# Mirror_TurnSignal.net
KiCad netlist of a schematic drawn in Altium Designer
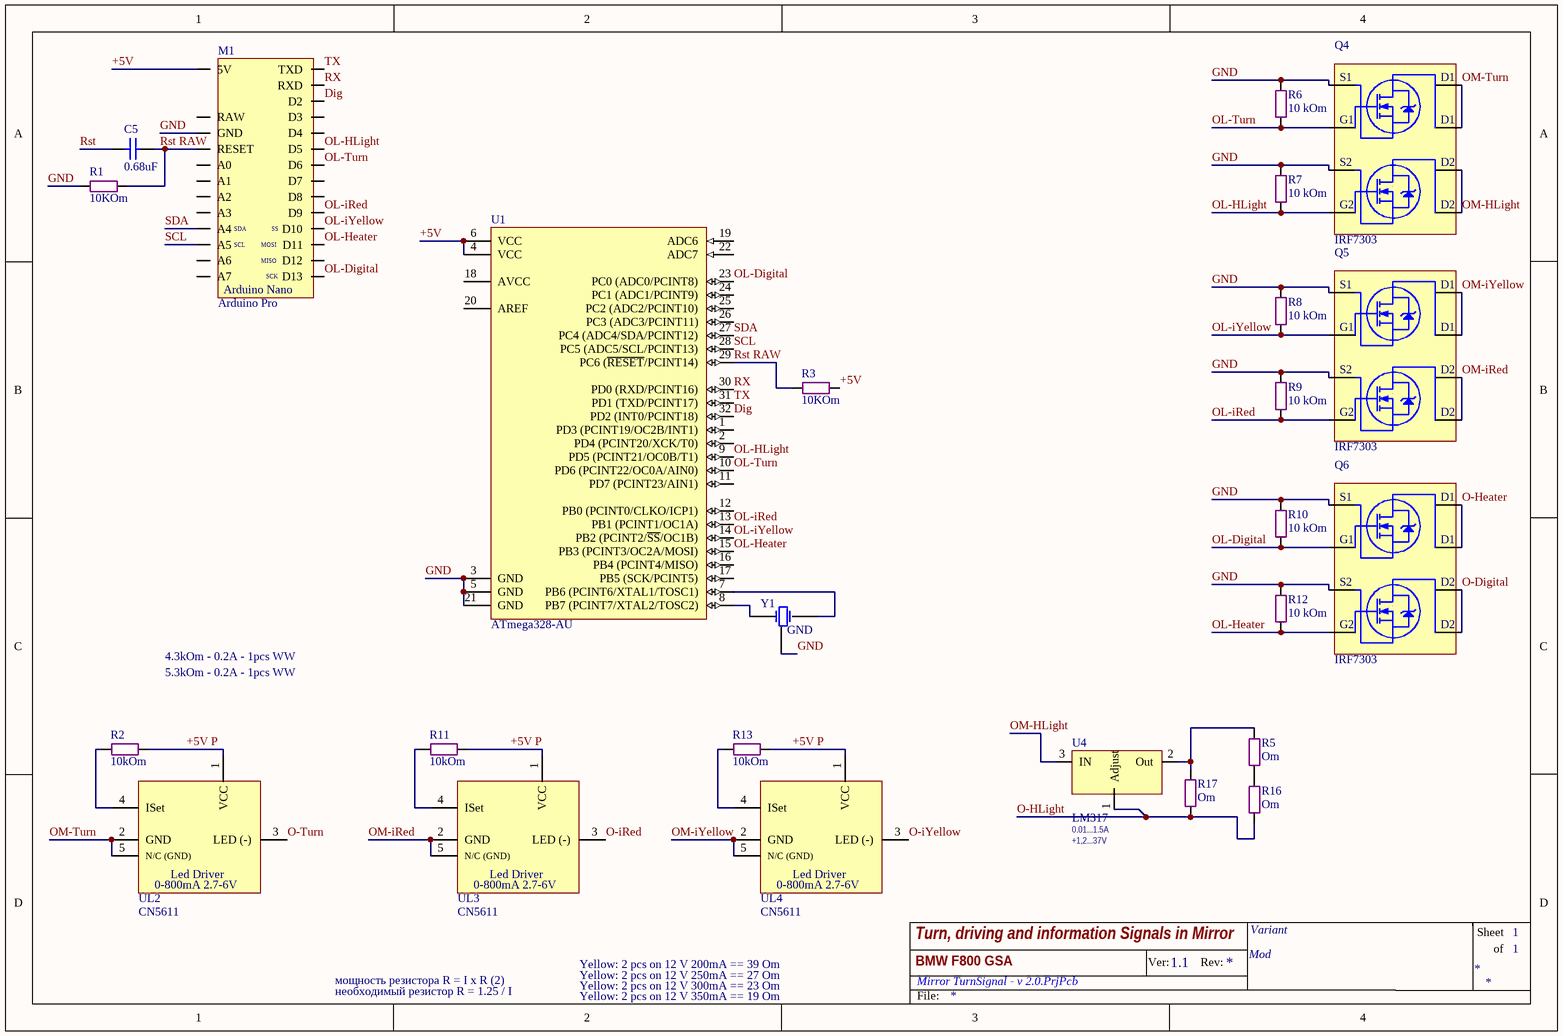
[diagram p0: Mirror TurnSignal.SchDoc]

(export (version "E")
  (design (tool "Eeschema 10.0.6"))
  (components
    (comp (ref "C5")
      (value "0.68uF")
      (footprint "Capacitor:SMD 0805 (2012)")
      (description "Capacitor")
      (libsource (lib "Capacitor") (part "Cap SMD 0402-1812"))
    )
    (comp (ref "M1")
      (value "Arduino Pro")
      (footprint "Modules:Arduino Pro Mini Low (no A0-3,6-7,D3)")
      (libsource (lib "Modules") (part "Arduino Pro Micro"))
    )
    (comp (ref "Q4")
      (value "IRF7303")
      (footprint "GeneralCases:SO8")
      (description "Dual N-Ch  30V - 0.05Ω - 4.9A")
      (fields (field (name "MANUFACTURER") "Farchild"))
      (libsource (lib "Transistor") (part "IRF7303"))
    )
    (comp (ref "Q5")
      (value "IRF7303")
      (footprint "GeneralCases:SO8")
      (description "Dual N-Ch  30V - 0.05Ω - 4.9A")
      (fields (field (name "MANUFACTURER") "Farchild"))
      (libsource (lib "Transistor") (part "IRF7303"))
    )
    (comp (ref "Q6")
      (value "IRF7303")
      (footprint "GeneralCases:SO8")
      (description "Dual N-Ch  30V - 0.05Ω - 4.9A")
      (fields (field (name "MANUFACTURER") "Farchild"))
      (libsource (lib "Transistor") (part "IRF7303"))
    )
    (comp (ref "R1")
      (value "10KOm")
      (footprint "PassiveComponents:SMD 0805 (2012)")
      (libsource (lib "PassiveComponents") (part "Res All Types"))
    )
    (comp (ref "R2")
      (value "10kOm")
      (footprint "PassiveComponents:SMD 0805 (2012)")
      (libsource (lib "PassiveComponents") (part "Res All Types"))
    )
    (comp (ref "R3")
      (value "10KOm")
      (footprint "PassiveComponents:SMD 0805 (2012)")
      (libsource (lib "PassiveComponents") (part "Res All Types"))
    )
    (comp (ref "R5")
      (value "Om")
      (footprint "PassiveComponents:Res 5W L22mm, p22.86")
      (description "5W Cement")
      (libsource (lib "PassiveComponents") (part "Res 5W"))
    )
    (comp (ref "R6")
      (value "10 kOm")
      (footprint "PassiveComponents:SMD 0805 (2012)")
      (libsource (lib "PassiveComponents") (part "Res All Types"))
    )
    (comp (ref "R7")
      (value "10 kOm")
      (footprint "PassiveComponents:SMD 0805 (2012)")
      (libsource (lib "PassiveComponents") (part "Res All Types"))
    )
    (comp (ref "R8")
      (value "10 kOm")
      (footprint "PassiveComponents:SMD 0805 (2012)")
      (libsource (lib "PassiveComponents") (part "Res All Types"))
    )
    (comp (ref "R9")
      (value "10 kOm")
      (footprint "PassiveComponents:SMD 0805 (2012)")
      (libsource (lib "PassiveComponents") (part "Res All Types"))
    )
    (comp (ref "R10")
      (value "10 kOm")
      (footprint "PassiveComponents:SMD 0805 (2012)")
      (libsource (lib "PassiveComponents") (part "Res All Types"))
    )
    (comp (ref "R11")
      (value "10kOm")
      (footprint "PassiveComponents:SMD 0805 (2012)")
      (libsource (lib "PassiveComponents") (part "Res All Types"))
    )
    (comp (ref "R12")
      (value "10 kOm")
      (footprint "PassiveComponents:SMD 0805 (2012)")
      (libsource (lib "PassiveComponents") (part "Res All Types"))
    )
    (comp (ref "R13")
      (value "10kOm")
      (footprint "PassiveComponents:SMD 0805 (2012)")
      (libsource (lib "PassiveComponents") (part "Res All Types"))
    )
    (comp (ref "R16")
      (value "Om")
      (footprint "PassiveComponents:Res 5W L22mm, p22.86")
      (description "5W Cement")
      (libsource (lib "PassiveComponents") (part "Res 5W"))
    )
    (comp (ref "R17")
      (value "Om")
      (footprint "PassiveComponents:Res 10W L48mm, p49mm")
      (description "10W Cement")
      (libsource (lib "PassiveComponents") (part "Res 10W"))
    )
    (comp (ref "U1")
      (value "ATmega328-AU")
      (footprint "32A_M")
      (fields (field (name "PUBLISHER") "Altium Limited"))
      (libsource (lib "Atmel Microcontroller 8-Bit megaAVR") (part "ATmega328-AU"))
    )
    (comp (ref "U4")
      (value "LM317")
      (footprint "GeneralCases:TO220 L")
      (description "Voltage Regulator")
      (fields (field (name "I OUTPUT (A) ADJUSTABLE") "0.01...1.5A") (field (name "V OUT") "+1,2...37V"))
      (libsource (lib "PowerAdjusment") (part "LM-317"))
    )
    (comp (ref "UL2")
      (value "CN5611")
      (footprint "GeneralCases:SOT-89-5")
      (description "Led Driver 0-800mA 2.7-6V")
      (fields (field (name "NAME") "CN5611"))
      (libsource (lib "Chips") (part "CN5611"))
    )
    (comp (ref "UL3")
      (value "CN5611")
      (footprint "GeneralCases:SOT-89-5")
      (description "Led Driver 0-800mA 2.7-6V")
      (fields (field (name "NAME") "CN5611"))
      (libsource (lib "Chips") (part "CN5611"))
    )
    (comp (ref "UL4")
      (value "CN5611")
      (footprint "GeneralCases:SOT-89-5")
      (description "Led Driver 0-800mA 2.7-6V")
      (fields (field (name "NAME") "CN5611"))
      (libsource (lib "Chips") (part "CN5611"))
    )
    (comp (ref "Y1")
      (value "16MHz")
      (footprint "PassiveComponents:XTAL - 3.2x1.2 SMD ws GND")
      (description "3 Pin with Capacitors")
      (libsource (lib "PassiveComponents") (part "XTAL ws CAP"))
    )
  )
  (nets
    (net (code "1") (name "/+5V") (class "Default")
      (node (ref "M1") (pin "5V") (pinfunction "5V_5V") (pintype "passive"))
      (node (ref "R3") (pin "2") (pinfunction "2_2") (pintype "passive"))
      (node (ref "U1") (pin "4") (pinfunction "VCC_4") (pintype "power_in"))
      (node (ref "U1") (pin "6") (pinfunction "VCC_6") (pintype "power_in"))
    )
    (net (code "2") (name "/+5V P") (class "Default")
      (node (ref "R11") (pin "1") (pinfunction "1_1") (pintype "passive"))
      (node (ref "R13") (pin "1") (pinfunction "1_1") (pintype "passive"))
      (node (ref "R2") (pin "1") (pinfunction "1_1") (pintype "passive"))
      (node (ref "UL2") (pin "1") (pinfunction "VCC_1") (pintype "power_in"))
      (node (ref "UL3") (pin "1") (pinfunction "VCC_1") (pintype "power_in"))
      (node (ref "UL4") (pin "1") (pinfunction "VCC_1") (pintype "power_in"))
    )
    (net (code "3") (name "/Dig") (class "Default")
      (node (ref "M1") (pin "D2") (pinfunction "D2_D2") (pintype "passive"))
      (node (ref "U1") (pin "32") (pinfunction "PD2_(INT0/PCINT18)_32") (pintype "bidirectional"))
    )
    (net (code "4") (name "/GND") (class "Default")
      (node (ref "M1") (pin "GND") (pinfunction "GND_GND") (pintype "passive"))
      (node (ref "Q4") (pin "1") (pinfunction "S_1") (pintype "passive"))
      (node (ref "Q4") (pin "3") (pinfunction "S_3") (pintype "passive"))
      (node (ref "Q5") (pin "1") (pinfunction "S_1") (pintype "passive"))
      (node (ref "Q5") (pin "3") (pinfunction "S_3") (pintype "passive"))
      (node (ref "Q6") (pin "1") (pinfunction "S_1") (pintype "passive"))
      (node (ref "Q6") (pin "3") (pinfunction "S_3") (pintype "passive"))
      (node (ref "R1") (pin "1") (pinfunction "1_1") (pintype "passive"))
      (node (ref "R10") (pin "2") (pinfunction "2_2") (pintype "passive"))
      (node (ref "R12") (pin "2") (pinfunction "2_2") (pintype "passive"))
      (node (ref "R6") (pin "2") (pinfunction "2_2") (pintype "passive"))
      (node (ref "R7") (pin "2") (pinfunction "2_2") (pintype "passive"))
      (node (ref "R8") (pin "2") (pinfunction "2_2") (pintype "passive"))
      (node (ref "R9") (pin "2") (pinfunction "2_2") (pintype "passive"))
      (node (ref "U1") (pin "21") (pinfunction "GND_21") (pintype "power_in"))
      (node (ref "U1") (pin "3") (pinfunction "GND_3") (pintype "power_in"))
      (node (ref "U1") (pin "5") (pinfunction "GND_5") (pintype "power_in"))
      (node (ref "Y1") (pin "3") (pinfunction "GND_3") (pintype "passive"))
    )
    (net (code "5") (name "/O-Digital") (class "Default")
      (node (ref "Q6") (pin "5") (pinfunction "D_5") (pintype "passive"))
      (node (ref "Q6") (pin "6") (pinfunction "D_6") (pintype "passive"))
    )
    (net (code "6") (name "/O-HLight") (class "Default")
      (node (ref "R16") (pin "1") (pinfunction "1_1") (pintype "passive"))
      (node (ref "R17") (pin "1") (pinfunction "1_1") (pintype "passive"))
      (node (ref "U4") (pin "1") (pinfunction "Adjust_1") (pintype "passive"))
    )
    (net (code "7") (name "/O-Heater") (class "Default")
      (node (ref "Q6") (pin "7") (pinfunction "D_7") (pintype "passive"))
      (node (ref "Q6") (pin "8") (pinfunction "D_8") (pintype "passive"))
    )
    (net (code "8") (name "/O-Turn") (class "Default")
      (node (ref "UL2") (pin "3") (pinfunction "LED_(-)_3") (pintype "power_in"))
    )
    (net (code "9") (name "/O-iRed") (class "Default")
      (node (ref "UL3") (pin "3") (pinfunction "LED_(-)_3") (pintype "power_in"))
    )
    (net (code "10") (name "/O-iYellow") (class "Default")
      (node (ref "UL4") (pin "3") (pinfunction "LED_(-)_3") (pintype "power_in"))
    )
    (net (code "11") (name "/OL-Digital") (class "Default")
      (node (ref "M1") (pin "D13") (pinfunction "D13_D13") (pintype "passive"))
      (node (ref "Q6") (pin "2") (pinfunction "G_2") (pintype "passive"))
      (node (ref "R10") (pin "1") (pinfunction "1_1") (pintype "passive"))
      (node (ref "U1") (pin "23") (pinfunction "PC0_(ADC0/PCINT8)_23") (pintype "bidirectional"))
    )
    (net (code "12") (name "/OL-HLight") (class "Default")
      (node (ref "M1") (pin "D5") (pinfunction "D5_D5") (pintype "passive"))
      (node (ref "Q4") (pin "4") (pinfunction "G_4") (pintype "passive"))
      (node (ref "R7") (pin "1") (pinfunction "1_1") (pintype "passive"))
      (node (ref "U1") (pin "9") (pinfunction "PD5_(PCINT21/OC0B/T1)_9") (pintype "bidirectional"))
    )
    (net (code "13") (name "/OL-Heater") (class "Default")
      (node (ref "M1") (pin "D11") (pinfunction "D11_D11") (pintype "passive"))
      (node (ref "Q6") (pin "4") (pinfunction "G_4") (pintype "passive"))
      (node (ref "R12") (pin "1") (pinfunction "1_1") (pintype "passive"))
      (node (ref "U1") (pin "15") (pinfunction "PB3_(PCINT3/OC2A/MOSI)_15") (pintype "bidirectional"))
    )
    (net (code "14") (name "/OL-Turn") (class "Default")
      (node (ref "M1") (pin "D6") (pinfunction "D6_D6") (pintype "passive"))
      (node (ref "Q4") (pin "2") (pinfunction "G_2") (pintype "passive"))
      (node (ref "R6") (pin "1") (pinfunction "1_1") (pintype "passive"))
      (node (ref "U1") (pin "10") (pinfunction "PD6_(PCINT22/OC0A/AIN0)_10") (pintype "bidirectional"))
    )
    (net (code "15") (name "/OL-iRed") (class "Default")
      (node (ref "M1") (pin "D9") (pinfunction "D9_D9") (pintype "passive"))
      (node (ref "Q5") (pin "4") (pinfunction "G_4") (pintype "passive"))
      (node (ref "R9") (pin "1") (pinfunction "1_1") (pintype "passive"))
      (node (ref "U1") (pin "13") (pinfunction "PB1_(PCINT1/OC1A)_13") (pintype "bidirectional"))
    )
    (net (code "16") (name "/OL-iYellow") (class "Default")
      (node (ref "M1") (pin "D10") (pinfunction "D10_D10") (pintype "passive"))
      (node (ref "Q5") (pin "2") (pinfunction "G_2") (pintype "passive"))
      (node (ref "R8") (pin "1") (pinfunction "1_1") (pintype "passive"))
      (node (ref "U1") (pin "14") (pinfunction "PB2_(PCINT2/~{SS}/OC1B)_14") (pintype "bidirectional"))
    )
    (net (code "17") (name "/OM-HLight") (class "Default")
      (node (ref "Q4") (pin "5") (pinfunction "D_5") (pintype "passive"))
      (node (ref "Q4") (pin "6") (pinfunction "D_6") (pintype "passive"))
      (node (ref "U4") (pin "3") (pinfunction "IN_3") (pintype "power_in"))
    )
    (net (code "18") (name "/OM-Turn") (class "Default")
      (node (ref "Q4") (pin "7") (pinfunction "D_7") (pintype "passive"))
      (node (ref "Q4") (pin "8") (pinfunction "D_8") (pintype "passive"))
      (node (ref "UL2") (pin "2") (pinfunction "GND_2") (pintype "power_in"))
      (node (ref "UL2") (pin "5") (pinfunction "N/C_(GND)_5") (pintype "power_in"))
    )
    (net (code "19") (name "/OM-iRed") (class "Default")
      (node (ref "Q5") (pin "5") (pinfunction "D_5") (pintype "passive"))
      (node (ref "Q5") (pin "6") (pinfunction "D_6") (pintype "passive"))
      (node (ref "UL3") (pin "2") (pinfunction "GND_2") (pintype "power_in"))
      (node (ref "UL3") (pin "5") (pinfunction "N/C_(GND)_5") (pintype "power_in"))
    )
    (net (code "20") (name "/OM-iYellow") (class "Default")
      (node (ref "Q5") (pin "7") (pinfunction "D_7") (pintype "passive"))
      (node (ref "Q5") (pin "8") (pinfunction "D_8") (pintype "passive"))
      (node (ref "UL4") (pin "2") (pinfunction "GND_2") (pintype "power_in"))
      (node (ref "UL4") (pin "5") (pinfunction "N/C_(GND)_5") (pintype "power_in"))
    )
    (net (code "21") (name "/RX") (class "Default")
      (node (ref "M1") (pin "RXD") (pinfunction "RXD_RXD") (pintype "passive"))
      (node (ref "U1") (pin "30") (pinfunction "PD0_(RXD/PCINT16)_30") (pintype "bidirectional"))
    )
    (net (code "22") (name "/Rst") (class "Default")
      (node (ref "C5") (pin "1") (pinfunction "1_1") (pintype "passive"))
    )
    (net (code "23") (name "/Rst RAW") (class "Default")
      (node (ref "C5") (pin "2") (pinfunction "2_2") (pintype "passive"))
      (node (ref "M1") (pin "RESET") (pinfunction "RESET_RESET") (pintype "passive"))
      (node (ref "R1") (pin "2") (pinfunction "2_2") (pintype "passive"))
      (node (ref "R3") (pin "1") (pinfunction "1_1") (pintype "passive"))
      (node (ref "U1") (pin "29") (pinfunction "PC6_(~{RESET}/PCINT14)_29") (pintype "bidirectional"))
    )
    (net (code "24") (name "/SCL") (class "Default")
      (node (ref "M1") (pin "A5") (pinfunction "A5_A5") (pintype "passive"))
      (node (ref "U1") (pin "28") (pinfunction "PC5_(ADC5/SCL/PCINT13)_28") (pintype "bidirectional"))
    )
    (net (code "25") (name "/SDA") (class "Default")
      (node (ref "M1") (pin "A4") (pinfunction "A4_A4") (pintype "passive"))
      (node (ref "U1") (pin "27") (pinfunction "PC4_(ADC4/SDA/PCINT12)_27") (pintype "bidirectional"))
    )
    (net (code "26") (name "/TX") (class "Default")
      (node (ref "M1") (pin "TXD") (pinfunction "TXD_TXD") (pintype "passive"))
      (node (ref "U1") (pin "31") (pinfunction "PD1_(TXD/PCINT17)_31") (pintype "bidirectional"))
    )
    (net (code "27") (name "Net-(R16-Pad2)") (class "Default")
      (node (ref "R16") (pin "2") (pinfunction "2_2") (pintype "passive"))
      (node (ref "R5") (pin "1") (pinfunction "1_1") (pintype "passive"))
    )
    (net (code "28") (name "Net-(U1-PB6_(PCINT6{slash}XTAL1{slash}TOSC1))") (class "Default")
      (node (ref "U1") (pin "7") (pinfunction "PB6_(PCINT6/XTAL1/TOSC1)_7") (pintype "bidirectional"))
      (node (ref "Y1") (pin "2") (pinfunction "OSC2_2") (pintype "passive"))
    )
    (net (code "29") (name "Net-(U1-PB7_(PCINT7{slash}XTAL2{slash}TOSC2))") (class "Default")
      (node (ref "U1") (pin "8") (pinfunction "PB7_(PCINT7/XTAL2/TOSC2)_8") (pintype "bidirectional"))
      (node (ref "Y1") (pin "1") (pinfunction "OSC1_1") (pintype "passive"))
    )
    (net (code "30") (name "Net-(U4-Out)") (class "Default")
      (node (ref "R17") (pin "2") (pinfunction "2_2") (pintype "passive"))
      (node (ref "R5") (pin "2") (pinfunction "2_2") (pintype "passive"))
      (node (ref "U4") (pin "2") (pinfunction "Out_2") (pintype "power_in"))
    )
    (net (code "31") (name "Net-(UL2-ISet)") (class "Default")
      (node (ref "R2") (pin "2") (pinfunction "2_2") (pintype "passive"))
      (node (ref "UL2") (pin "4") (pinfunction "ISet_4") (pintype "power_in"))
    )
    (net (code "32") (name "Net-(UL3-ISet)") (class "Default")
      (node (ref "R11") (pin "2") (pinfunction "2_2") (pintype "passive"))
      (node (ref "UL3") (pin "4") (pinfunction "ISet_4") (pintype "power_in"))
    )
    (net (code "33") (name "Net-(UL4-ISet)") (class "Default")
      (node (ref "R13") (pin "2") (pinfunction "2_2") (pintype "passive"))
      (node (ref "UL4") (pin "4") (pinfunction "ISet_4") (pintype "power_in"))
    )
    (net (code "34") (name "unconnected-(M1-PadA0)") (class "Default")
      (node (ref "M1") (pin "A0") (pinfunction "A0_A0") (pintype "passive"))
    )
    (net (code "35") (name "unconnected-(M1-PadA1)") (class "Default")
      (node (ref "M1") (pin "A1") (pinfunction "A1_A1") (pintype "passive"))
    )
    (net (code "36") (name "unconnected-(M1-PadA2)") (class "Default")
      (node (ref "M1") (pin "A2") (pinfunction "A2_A2") (pintype "passive"))
    )
    (net (code "37") (name "unconnected-(M1-PadA3)") (class "Default")
      (node (ref "M1") (pin "A3") (pinfunction "A3_A3") (pintype "passive"))
    )
    (net (code "38") (name "unconnected-(M1-PadA6)") (class "Default")
      (node (ref "M1") (pin "A6") (pinfunction "A6_A6") (pintype "passive"))
    )
    (net (code "39") (name "unconnected-(M1-PadA7)") (class "Default")
      (node (ref "M1") (pin "A7") (pinfunction "A7_A7") (pintype "passive"))
    )
    (net (code "40") (name "unconnected-(M1-PadD3)") (class "Default")
      (node (ref "M1") (pin "D3") (pinfunction "D3_D3") (pintype "passive"))
    )
    (net (code "41") (name "unconnected-(M1-PadD4)") (class "Default")
      (node (ref "M1") (pin "D4") (pinfunction "D4_D4") (pintype "passive"))
    )
    (net (code "42") (name "unconnected-(M1-PadD7)") (class "Default")
      (node (ref "M1") (pin "D7") (pinfunction "D7_D7") (pintype "passive"))
    )
    (net (code "43") (name "unconnected-(M1-PadD8)") (class "Default")
      (node (ref "M1") (pin "D8") (pinfunction "D8_D8") (pintype "passive"))
    )
    (net (code "44") (name "unconnected-(M1-PadD12)") (class "Default")
      (node (ref "M1") (pin "D12") (pinfunction "D12_D12") (pintype "passive"))
    )
    (net (code "45") (name "unconnected-(M1-PadRAW)") (class "Default")
      (node (ref "M1") (pin "RAW") (pinfunction "RAW_RAW") (pintype "passive"))
    )
    (net (code "46") (name "unconnected-(U1-ADC6-Pad19)") (class "Default")
      (node (ref "U1") (pin "19") (pinfunction "ADC6_19") (pintype "input"))
    )
    (net (code "47") (name "unconnected-(U1-ADC7-Pad22)") (class "Default")
      (node (ref "U1") (pin "22") (pinfunction "ADC7_22") (pintype "input"))
    )
    (net (code "48") (name "unconnected-(U1-AREF-Pad20)") (class "Default")
      (node (ref "U1") (pin "20") (pinfunction "AREF_20") (pintype "passive"))
    )
    (net (code "49") (name "unconnected-(U1-AVCC-Pad18)") (class "Default")
      (node (ref "U1") (pin "18") (pinfunction "AVCC_18") (pintype "power_in"))
    )
    (net (code "50") (name "unconnected-(U1-PB0_(PCINT0{slash}CLKO{slash}ICP1)-Pad12)") (class "Default")
      (node (ref "U1") (pin "12") (pinfunction "PB0_(PCINT0/CLKO/ICP1)_12") (pintype "bidirectional"))
    )
    (net (code "51") (name "unconnected-(U1-PB4_(PCINT4{slash}MISO)-Pad16)") (class "Default")
      (node (ref "U1") (pin "16") (pinfunction "PB4_(PCINT4/MISO)_16") (pintype "bidirectional"))
    )
    (net (code "52") (name "unconnected-(U1-PB5_(SCK{slash}PCINT5)-Pad17)") (class "Default")
      (node (ref "U1") (pin "17") (pinfunction "PB5_(SCK/PCINT5)_17") (pintype "bidirectional"))
    )
    (net (code "53") (name "unconnected-(U1-PC1_(ADC1{slash}PCINT9)-Pad24)") (class "Default")
      (node (ref "U1") (pin "24") (pinfunction "PC1_(ADC1/PCINT9)_24") (pintype "bidirectional"))
    )
    (net (code "54") (name "unconnected-(U1-PC2_(ADC2{slash}PCINT10)-Pad25)") (class "Default")
      (node (ref "U1") (pin "25") (pinfunction "PC2_(ADC2/PCINT10)_25") (pintype "bidirectional"))
    )
    (net (code "55") (name "unconnected-(U1-PC3_(ADC3{slash}PCINT11)-Pad26)") (class "Default")
      (node (ref "U1") (pin "26") (pinfunction "PC3_(ADC3/PCINT11)_26") (pintype "bidirectional"))
    )
    (net (code "56") (name "unconnected-(U1-PD3_(PCINT19{slash}OC2B{slash}INT1)-Pad1)") (class "Default")
      (node (ref "U1") (pin "1") (pinfunction "PD3_(PCINT19/OC2B/INT1)_1") (pintype "bidirectional"))
    )
    (net (code "57") (name "unconnected-(U1-PD4_(PCINT20{slash}XCK{slash}T0)-Pad2)") (class "Default")
      (node (ref "U1") (pin "2") (pinfunction "PD4_(PCINT20/XCK/T0)_2") (pintype "bidirectional"))
    )
    (net (code "58") (name "unconnected-(U1-PD7_(PCINT23{slash}AIN1)-Pad11)") (class "Default")
      (node (ref "U1") (pin "11") (pinfunction "PD7_(PCINT23/AIN1)_11") (pintype "bidirectional"))
    )
  )
)
